# 01_Connectors.net
KiCad netlist of a schematic drawn in Altium Designer
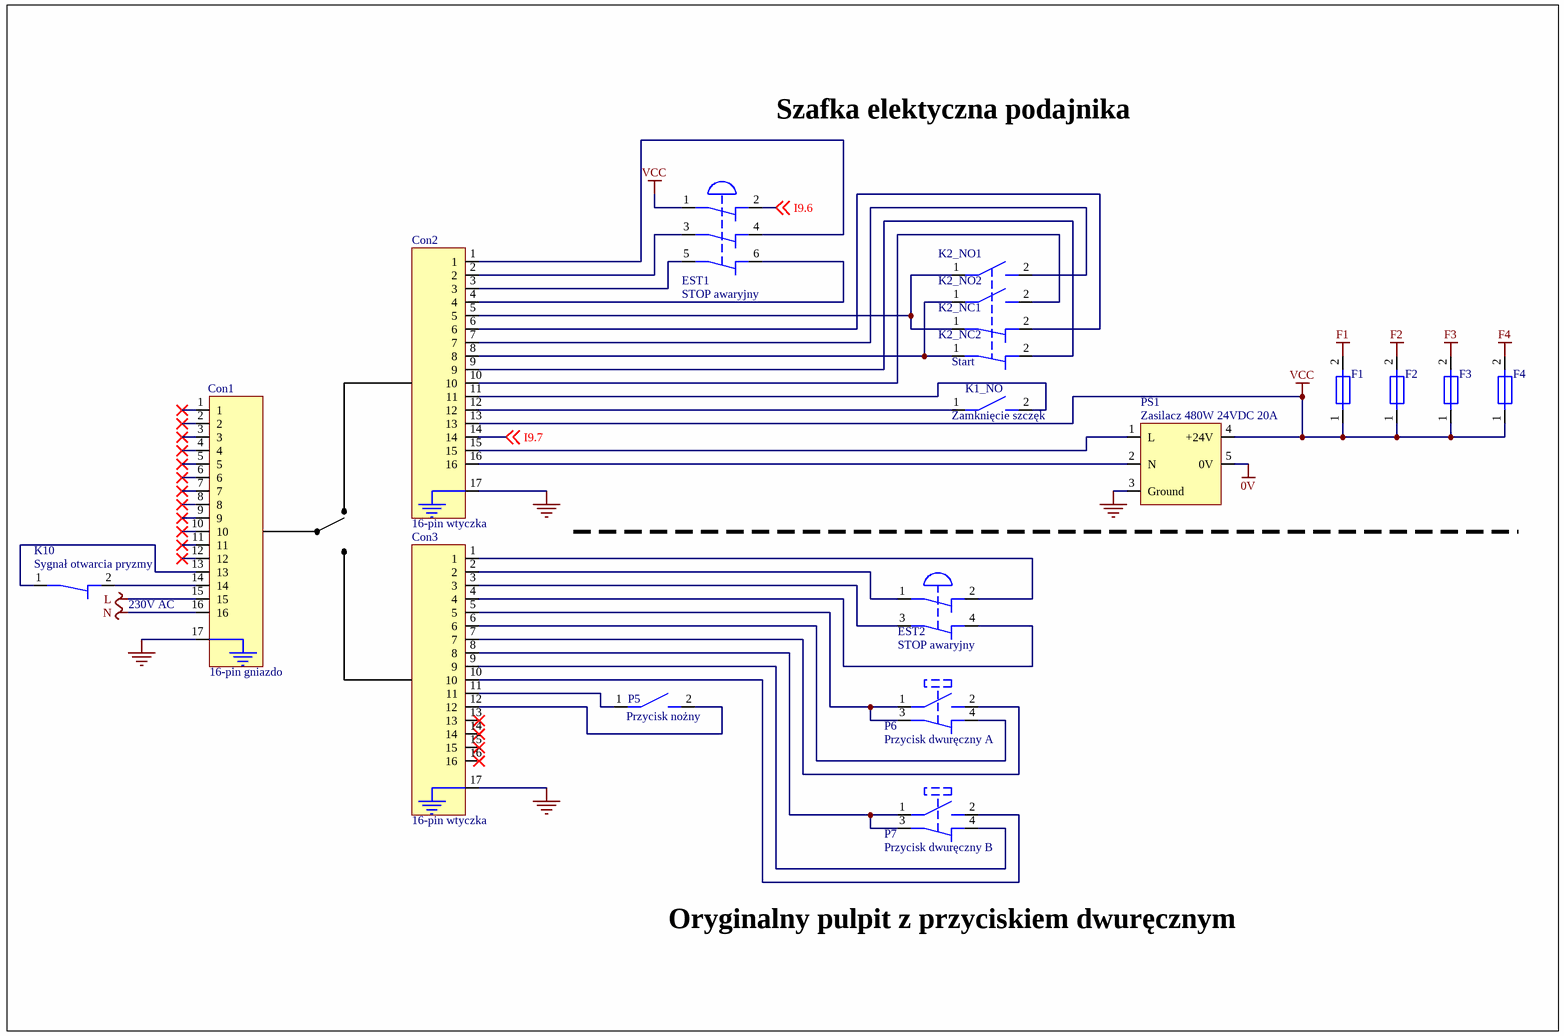
[diagram p0: [01] Connectors.SchDoc]

(export (version "E")
  (design (tool "Eeschema 10.0.6"))
  (components
    (comp (ref "Con1") (value "16-pin gniazdo") (libsource (lib "Schlib1") (part "16-pin in connector")))
    (comp (ref "Con2") (value "16-pin wtyczka") (libsource (lib "Schlib1") (part "16-pin out connector")))
    (comp (ref "Con3") (value "16-pin wtyczka") (libsource (lib "Schlib1") (part "16-pin out connector")))
    (comp (ref "EST1") (value "STOP awaryjny") (libsource (lib "Schlib1") (part "E-STOP 3 line")))
    (comp (ref "EST2") (value "STOP awaryjny") (libsource (lib "Schlib1") (part "E-STOP 2 line")))
    (comp (ref "F1") (value "?A") (libsource (lib "Schlib1") (part "Fuse")))
    (comp (ref "F2") (value "?A") (libsource (lib "Schlib1") (part "Fuse")))
    (comp (ref "F3") (value "?A") (libsource (lib "Schlib1") (part "Fuse")))
    (comp (ref "F4") (value "?A") (libsource (lib "Schlib1") (part "Fuse")))
    (comp (ref "K1_NO") (value "Zamknięcie szczęk") (libsource (lib "Schlib1") (part "NO")))
    (comp (ref "K2_NC1") (value "NC") (libsource (lib "Schlib1") (part "NC")))
    (comp (ref "K2_NC2") (value "NC") (libsource (lib "Schlib1") (part "NC")))
    (comp (ref "K2_NO1") (value "Start") (libsource (lib "Schlib1") (part "NO")))
    (comp (ref "K2_NO2") (value "NO") (libsource (lib "Schlib1") (part "NO")))
    (comp (ref "K10") (value "Sygnał otwarcia pryzmy") (libsource (lib "Schlib1") (part "NC")))
    (comp (ref "P5") (value "Przycisk nożny") (libsource (lib "Schlib1") (part "NO")))
    (comp (ref "P6") (value "Przycisk dwuręczny A") (libsource (lib "Schlib1") (part "Button NO+NC")))
    (comp (ref "P7") (value "Przycisk dwuręczny B") (libsource (lib "Schlib1") (part "Button NO+NC")))
    (comp (ref "PS1") (value "Zasilacz 480W 24VDC 20A") (libsource (lib "Schlib1") (part "Power supply")))
  )
  (nets
    (net (code "1") (name "0V") (class "Default")
      (node (ref "PS1") (pin "5") (pinfunction "0V_5") (pintype "passive"))
    )
    (net (code "2") (name "F1") (class "Default")
      (node (ref "F1") (pin "2") (pinfunction "21_2") (pintype "passive"))
    )
    (net (code "3") (name "F2") (class "Default")
      (node (ref "F2") (pin "2") (pinfunction "21_2") (pintype "passive"))
    )
    (net (code "4") (name "F3") (class "Default")
      (node (ref "F3") (pin "2") (pinfunction "21_2") (pintype "passive"))
    )
    (net (code "5") (name "F4") (class "Default")
      (node (ref "F4") (pin "2") (pinfunction "21_2") (pintype "passive"))
    )
    (net (code "6") (name "GND") (class "Default")
      (node (ref "Con1") (pin "17") (pinfunction "17_17") (pintype "passive"))
      (node (ref "Con2") (pin "17") (pinfunction "Ground_17") (pintype "passive"))
      (node (ref "Con3") (pin "17") (pinfunction "Ground_17") (pintype "passive"))
      (node (ref "PS1") (pin "3") (pinfunction "Ground_3") (pintype "passive"))
    )
    (net (code "7") (name "I9.6") (class "Default")
      (node (ref "EST1") (pin "2") (pinfunction "*_2") (pintype "passive"))
    )
    (net (code "8") (name "I9.7") (class "Default")
      (node (ref "Con2") (pin "14") (pinfunction "14_14") (pintype "passive"))
    )
    (net (code "9") (name "L") (class "Default")
      (node (ref "Con1") (pin "15") (pinfunction "15_15") (pintype "passive"))
    )
    (net (code "10") (name "N") (class "Default")
      (node (ref "Con1") (pin "16") (pinfunction "16_16") (pintype "passive"))
    )
    (net (code "11") (name "Net-(Con2-Pad1)") (class "Default")
      (node (ref "Con2") (pin "1") (pinfunction "1_1") (pintype "passive"))
      (node (ref "EST1") (pin "4") (pinfunction "*_4") (pintype "passive"))
    )
    (net (code "12") (name "Net-(Con2-Pad2)") (class "Default")
      (node (ref "Con2") (pin "2") (pinfunction "2_2") (pintype "passive"))
      (node (ref "EST1") (pin "3") (pinfunction "*_3") (pintype "passive"))
    )
    (net (code "13") (name "Net-(Con2-Pad3)") (class "Default")
      (node (ref "Con2") (pin "3") (pinfunction "3_3") (pintype "passive"))
      (node (ref "EST1") (pin "5") (pinfunction "*_5") (pintype "passive"))
    )
    (net (code "14") (name "Net-(Con2-Pad4)") (class "Default")
      (node (ref "Con2") (pin "4") (pinfunction "4_4") (pintype "passive"))
      (node (ref "EST1") (pin "6") (pinfunction "*_6") (pintype "passive"))
    )
    (net (code "15") (name "Net-(Con2-Pad7)") (class "Default")
      (node (ref "Con2") (pin "7") (pinfunction "7_7") (pintype "passive"))
      (node (ref "K2_NO1") (pin "2") (pinfunction "*_2") (pintype "passive"))
    )
    (net (code "16") (name "Net-(Con2-Pad10)") (class "Default")
      (node (ref "Con2") (pin "10") (pinfunction "10_10") (pintype "passive"))
      (node (ref "K2_NO2") (pin "2") (pinfunction "*_2") (pintype "passive"))
    )
    (net (code "17") (name "Net-(Con2-Pad11)") (class "Default")
      (node (ref "Con2") (pin "11") (pinfunction "11_11") (pintype "passive"))
      (node (ref "K1_NO") (pin "2") (pinfunction "*_2") (pintype "passive"))
    )
    (net (code "18") (name "Net-(Con2-Pad12)") (class "Default")
      (node (ref "Con2") (pin "12") (pinfunction "12_12") (pintype "passive"))
      (node (ref "K1_NO") (pin "1") (pinfunction "*_1") (pintype "passive"))
    )
    (net (code "19") (name "Net-(Con3-Pad1)") (class "Default")
      (node (ref "Con3") (pin "1") (pinfunction "1_1") (pintype "passive"))
      (node (ref "EST2") (pin "2") (pinfunction "*_2") (pintype "passive"))
    )
    (net (code "20") (name "Net-(Con3-Pad2)") (class "Default")
      (node (ref "Con3") (pin "2") (pinfunction "2_2") (pintype "passive"))
      (node (ref "EST2") (pin "1") (pinfunction "*_1") (pintype "passive"))
    )
    (net (code "21") (name "Net-(Con3-Pad3)") (class "Default")
      (node (ref "Con3") (pin "3") (pinfunction "3_3") (pintype "passive"))
      (node (ref "EST2") (pin "3") (pinfunction "*_3") (pintype "passive"))
    )
    (net (code "22") (name "Net-(Con3-Pad4)") (class "Default")
      (node (ref "Con3") (pin "4") (pinfunction "4_4") (pintype "passive"))
      (node (ref "EST2") (pin "4") (pinfunction "*_4") (pintype "passive"))
    )
    (net (code "23") (name "Net-(Con3-Pad5)") (class "Default")
      (node (ref "Con3") (pin "5") (pinfunction "5_5") (pintype "passive"))
      (node (ref "P6") (pin "1") (pinfunction "*_1") (pintype "passive"))
      (node (ref "P6") (pin "3") (pinfunction "*_3") (pintype "passive"))
    )
    (net (code "24") (name "Net-(Con3-Pad6)") (class "Default")
      (node (ref "Con3") (pin "6") (pinfunction "6_6") (pintype "passive"))
      (node (ref "P6") (pin "4") (pinfunction "*_4") (pintype "passive"))
    )
    (net (code "25") (name "Net-(Con3-Pad7)") (class "Default")
      (node (ref "Con3") (pin "7") (pinfunction "7_7") (pintype "passive"))
      (node (ref "P6") (pin "2") (pinfunction "*_2") (pintype "passive"))
    )
    (net (code "26") (name "Net-(Con3-Pad8)") (class "Default")
      (node (ref "Con3") (pin "8") (pinfunction "8_8") (pintype "passive"))
      (node (ref "P7") (pin "1") (pinfunction "*_1") (pintype "passive"))
      (node (ref "P7") (pin "3") (pinfunction "*_3") (pintype "passive"))
    )
    (net (code "27") (name "Net-(Con3-Pad9)") (class "Default")
      (node (ref "Con3") (pin "9") (pinfunction "9_9") (pintype "passive"))
      (node (ref "P7") (pin "4") (pinfunction "*_4") (pintype "passive"))
    )
    (net (code "28") (name "Net-(Con3-Pad10)") (class "Default")
      (node (ref "Con3") (pin "10") (pinfunction "10_10") (pintype "passive"))
      (node (ref "P7") (pin "2") (pinfunction "*_2") (pintype "passive"))
    )
    (net (code "29") (name "Net-(Con3-Pad11)") (class "Default")
      (node (ref "Con3") (pin "11") (pinfunction "11_11") (pintype "passive"))
      (node (ref "P5") (pin "1") (pinfunction "*_1") (pintype "passive"))
    )
    (net (code "30") (name "Net-(Con3-Pad12)") (class "Default")
      (node (ref "Con3") (pin "12") (pinfunction "12_12") (pintype "passive"))
      (node (ref "P5") (pin "2") (pinfunction "*_2") (pintype "passive"))
    )
    (net (code "31") (name "Net-(K2_NC1-18)") (class "Default")
      (node (ref "Con2") (pin "5") (pinfunction "5_5") (pintype "passive"))
      (node (ref "K2_NC1") (pin "1") (pinfunction "18_1") (pintype "passive"))
      (node (ref "K2_NO1") (pin "1") (pinfunction "*_1") (pintype "passive"))
    )
    (net (code "32") (name "Net-(K2_NC1-19)") (class "Default")
      (node (ref "Con2") (pin "6") (pinfunction "6_6") (pintype "passive"))
      (node (ref "K2_NC1") (pin "2") (pinfunction "19_2") (pintype "passive"))
    )
    (net (code "33") (name "Net-(K2_NC2-18)") (class "Default")
      (node (ref "Con2") (pin "8") (pinfunction "8_8") (pintype "passive"))
      (node (ref "K2_NC2") (pin "1") (pinfunction "18_1") (pintype "passive"))
      (node (ref "K2_NO2") (pin "1") (pinfunction "*_1") (pintype "passive"))
    )
    (net (code "34") (name "Net-(K2_NC2-19)") (class "Default")
      (node (ref "Con2") (pin "9") (pinfunction "9_9") (pintype "passive"))
      (node (ref "K2_NC2") (pin "2") (pinfunction "19_2") (pintype "passive"))
    )
    (net (code "35") (name "Net-(K10-18)") (class "Default")
      (node (ref "Con1") (pin "13") (pinfunction "13_13") (pintype "passive"))
      (node (ref "K10") (pin "1") (pinfunction "18_1") (pintype "passive"))
    )
    (net (code "36") (name "Net-(K10-19)") (class "Default")
      (node (ref "Con1") (pin "14") (pinfunction "14_14") (pintype "passive"))
      (node (ref "K10") (pin "2") (pinfunction "19_2") (pintype "passive"))
    )
    (net (code "37") (name "Net-(PS1-L)") (class "Default")
      (node (ref "Con2") (pin "15") (pinfunction "15_15") (pintype "passive"))
      (node (ref "PS1") (pin "1") (pinfunction "L_1") (pintype "passive"))
    )
    (net (code "38") (name "Net-(PS1-N)") (class "Default")
      (node (ref "Con2") (pin "16") (pinfunction "16_16") (pintype "passive"))
      (node (ref "PS1") (pin "2") (pinfunction "N_2") (pintype "passive"))
    )
    (net (code "39") (name "VCC") (class "Default")
      (node (ref "Con2") (pin "13") (pinfunction "13_13") (pintype "passive"))
      (node (ref "EST1") (pin "1") (pinfunction "*_1") (pintype "passive"))
      (node (ref "F1") (pin "1") (pinfunction "20_1") (pintype "passive"))
      (node (ref "F2") (pin "1") (pinfunction "20_1") (pintype "passive"))
      (node (ref "F3") (pin "1") (pinfunction "20_1") (pintype "passive"))
      (node (ref "F4") (pin "1") (pinfunction "20_1") (pintype "passive"))
      (node (ref "PS1") (pin "4") (pinfunction "+24V_4") (pintype "passive"))
    )
    (net (code "40") (name "unconnected-(Con1-Pad1)") (class "Default")
      (node (ref "Con1") (pin "1") (pinfunction "1_1") (pintype "passive+no_connect"))
    )
    (net (code "41") (name "unconnected-(Con1-Pad2)") (class "Default")
      (node (ref "Con1") (pin "2") (pinfunction "2_2") (pintype "passive+no_connect"))
    )
    (net (code "42") (name "unconnected-(Con1-Pad3)") (class "Default")
      (node (ref "Con1") (pin "3") (pinfunction "3_3") (pintype "passive+no_connect"))
    )
    (net (code "43") (name "unconnected-(Con1-Pad4)") (class "Default")
      (node (ref "Con1") (pin "4") (pinfunction "4_4") (pintype "passive+no_connect"))
    )
    (net (code "44") (name "unconnected-(Con1-Pad5)") (class "Default")
      (node (ref "Con1") (pin "5") (pinfunction "5_5") (pintype "passive+no_connect"))
    )
    (net (code "45") (name "unconnected-(Con1-Pad6)") (class "Default")
      (node (ref "Con1") (pin "6") (pinfunction "6_6") (pintype "passive+no_connect"))
    )
    (net (code "46") (name "unconnected-(Con1-Pad7)") (class "Default")
      (node (ref "Con1") (pin "7") (pinfunction "7_7") (pintype "passive+no_connect"))
    )
    (net (code "47") (name "unconnected-(Con1-Pad8)") (class "Default")
      (node (ref "Con1") (pin "8") (pinfunction "8_8") (pintype "passive+no_connect"))
    )
    (net (code "48") (name "unconnected-(Con1-Pad9)") (class "Default")
      (node (ref "Con1") (pin "9") (pinfunction "9_9") (pintype "passive+no_connect"))
    )
    (net (code "49") (name "unconnected-(Con1-Pad10)") (class "Default")
      (node (ref "Con1") (pin "10") (pinfunction "10_10") (pintype "passive+no_connect"))
    )
    (net (code "50") (name "unconnected-(Con1-Pad11)") (class "Default")
      (node (ref "Con1") (pin "11") (pinfunction "11_11") (pintype "passive+no_connect"))
    )
    (net (code "51") (name "unconnected-(Con1-Pad12)") (class "Default")
      (node (ref "Con1") (pin "12") (pinfunction "12_12") (pintype "passive+no_connect"))
    )
    (net (code "52") (name "unconnected-(Con3-Pad13)") (class "Default")
      (node (ref "Con3") (pin "13") (pinfunction "13_13") (pintype "passive+no_connect"))
    )
    (net (code "53") (name "unconnected-(Con3-Pad14)") (class "Default")
      (node (ref "Con3") (pin "14") (pinfunction "14_14") (pintype "passive+no_connect"))
    )
    (net (code "54") (name "unconnected-(Con3-Pad15)") (class "Default")
      (node (ref "Con3") (pin "15") (pinfunction "15_15") (pintype "passive+no_connect"))
    )
    (net (code "55") (name "unconnected-(Con3-Pad16)") (class "Default")
      (node (ref "Con3") (pin "16") (pinfunction "16_16") (pintype "passive+no_connect"))
    )
  )
)
